# amplifier2.net
KiCad netlist of a schematic drawn in EAGLE
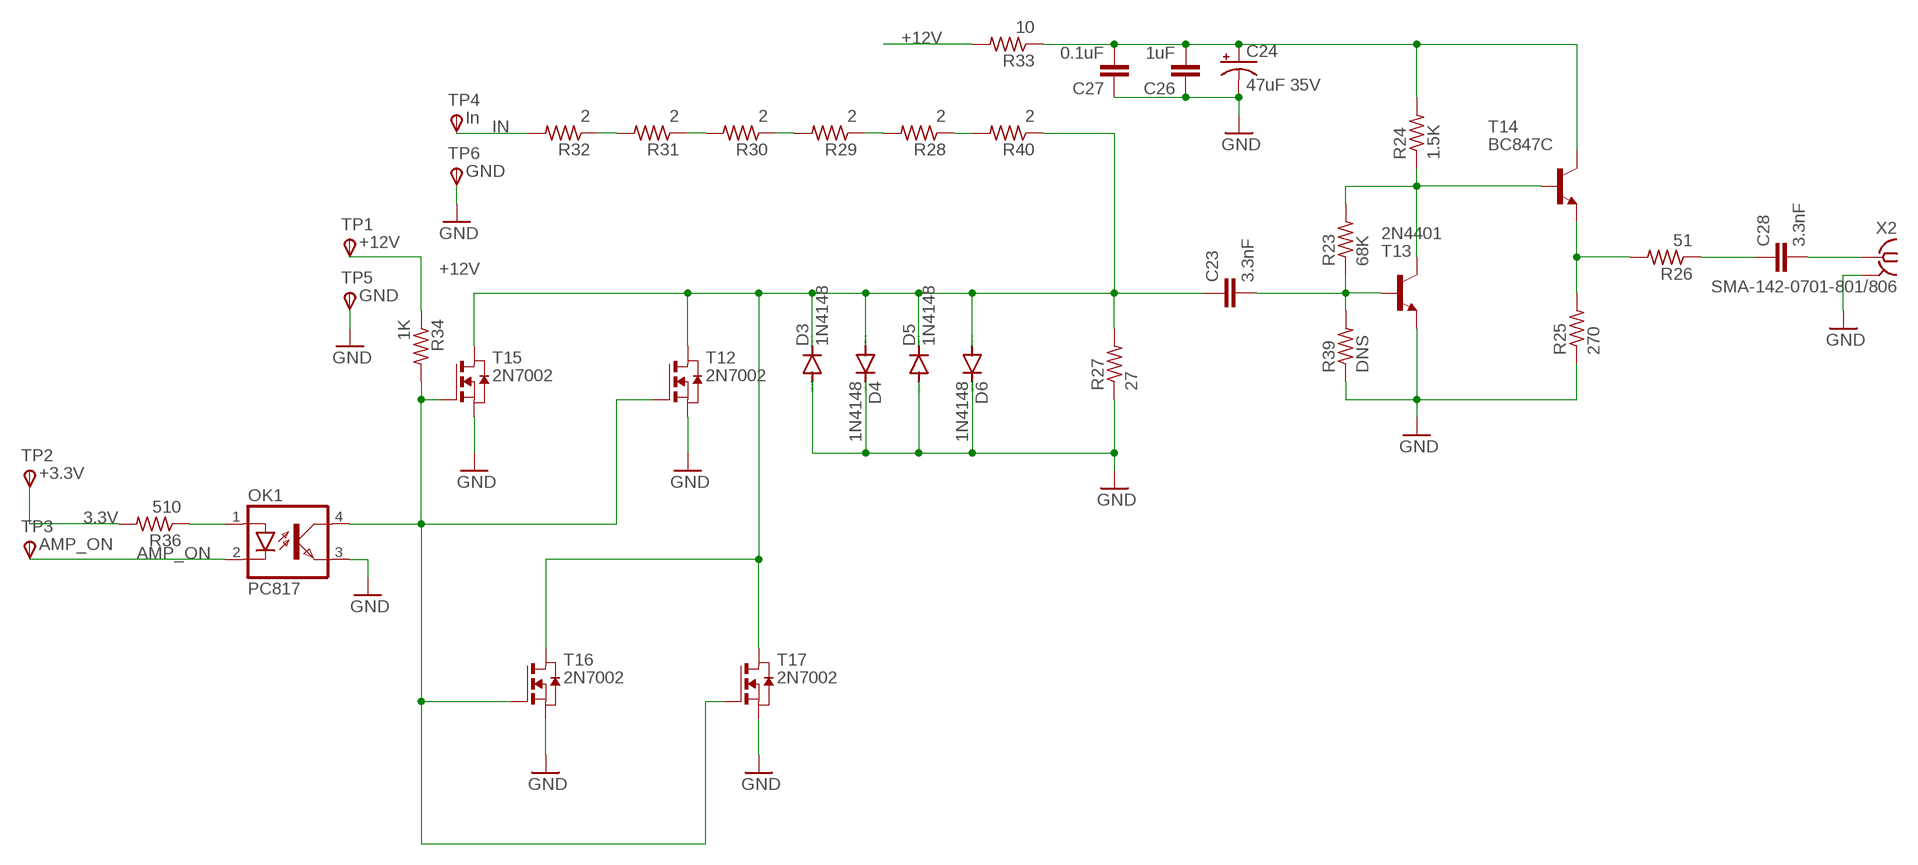
[diagram p0: schematic, sheet 1]

(export (version "E")
  (design (tool "Eeschema 10.0.6"))
  (components
    (comp (ref "C23")
      (value "3.3nF")
      (footprint "eagle-import:C0805")
      (libsource (lib "eagle-import") (part "C-EUC0805"))
    )
    (comp (ref "C24")
      (value "47uF 35V")
      (footprint "eagle-import:153CLV-1010")
      (libsource (lib "eagle-import") (part "CPOL-US153CLV-1010"))
    )
    (comp (ref "C26")
      (value "1uF")
      (footprint "eagle-import:C0805")
      (libsource (lib "eagle-import") (part "C-EUC0805"))
    )
    (comp (ref "C27")
      (value "0.1uF")
      (footprint "eagle-import:C0805")
      (libsource (lib "eagle-import") (part "C-EUC0805"))
    )
    (comp (ref "C28")
      (value "3.3nF")
      (footprint "eagle-import:C0805")
      (libsource (lib "eagle-import") (part "C-EUC0805"))
    )
    (comp (ref "D3")
      (value "1N4148")
      (footprint "eagle-import:MINIMELF")
      (libsource (lib "eagle-import") (part "DIODE-MINIMELF"))
    )
    (comp (ref "D4")
      (value "1N4148")
      (footprint "eagle-import:MINIMELF")
      (libsource (lib "eagle-import") (part "DIODE-MINIMELF"))
    )
    (comp (ref "D5")
      (value "1N4148")
      (footprint "eagle-import:MINIMELF")
      (libsource (lib "eagle-import") (part "DIODE-MINIMELF"))
    )
    (comp (ref "D6")
      (value "1N4148")
      (footprint "eagle-import:MINIMELF")
      (libsource (lib "eagle-import") (part "DIODE-MINIMELF"))
    )
    (comp (ref "OK1")
      (value "PC817")
      (footprint "eagle-import:DIL04")
      (fields (field (name "MPN") "PC817X4J000F"))
      (libsource (lib "eagle-import") (part "PC817"))
    )
    (comp (ref "R23")
      (value "68K")
      (footprint "eagle-import:R1206W")
      (libsource (lib "eagle-import") (part "R-US_R1206W"))
    )
    (comp (ref "R24")
      (value "1.5K")
      (footprint "eagle-import:R1206W")
      (libsource (lib "eagle-import") (part "R-US_R1206W"))
    )
    (comp (ref "R25")
      (value "270")
      (footprint "eagle-import:R1206W")
      (libsource (lib "eagle-import") (part "R-US_R1206W"))
    )
    (comp (ref "R26")
      (value "51")
      (footprint "eagle-import:R1206W")
      (libsource (lib "eagle-import") (part "R-US_R1206W"))
    )
    (comp (ref "R27")
      (value "27")
      (footprint "eagle-import:R1206W")
      (libsource (lib "eagle-import") (part "R-US_R1206W"))
    )
    (comp (ref "R28")
      (value "2")
      (footprint "eagle-import:R1206W")
      (libsource (lib "eagle-import") (part "R-US_R1206W"))
    )
    (comp (ref "R29")
      (value "2")
      (footprint "eagle-import:R1206W")
      (libsource (lib "eagle-import") (part "R-US_R1206W"))
    )
    (comp (ref "R30")
      (value "2")
      (footprint "eagle-import:R1206W")
      (libsource (lib "eagle-import") (part "R-US_R1206W"))
    )
    (comp (ref "R31")
      (value "2")
      (footprint "eagle-import:R1206W")
      (libsource (lib "eagle-import") (part "R-US_R1206W"))
    )
    (comp (ref "R32")
      (value "2")
      (footprint "eagle-import:R1206W")
      (libsource (lib "eagle-import") (part "R-US_R1206W"))
    )
    (comp (ref "R33")
      (value "10")
      (footprint "eagle-import:R1206W")
      (libsource (lib "eagle-import") (part "R-US_R1206W"))
    )
    (comp (ref "R34")
      (value "1K")
      (footprint "eagle-import:R1206W")
      (libsource (lib "eagle-import") (part "R-US_R1206W"))
    )
    (comp (ref "R36")
      (value "510")
      (footprint "eagle-import:R1206W")
      (libsource (lib "eagle-import") (part "R-US_R1206W"))
    )
    (comp (ref "R39")
      (value "DNS")
      (footprint "eagle-import:R1206W")
      (libsource (lib "eagle-import") (part "R-US_R1206W"))
    )
    (comp (ref "R40")
      (value "2")
      (footprint "eagle-import:R1206W")
      (libsource (lib "eagle-import") (part "R-US_R1206W"))
    )
    (comp (ref "T12")
      (value "2N7002")
      (footprint "eagle-import:SOT-23")
      (libsource (lib "eagle-import") (part "NMOSSOT23"))
    )
    (comp (ref "T13")
      (value "2N4401")
      (footprint "eagle-import:TO92-EBC")
      (libsource (lib "eagle-import") (part "-NPN-TO92-EBC2N4401"))
    )
    (comp (ref "T14")
      (value "BC847C")
      (footprint "eagle-import:SOT23-BEC")
      (libsource (lib "eagle-import") (part "transistor_402_-NPN-SOT23-BECBC847C"))
    )
    (comp (ref "T15")
      (value "2N7002")
      (footprint "eagle-import:SOT-23")
      (libsource (lib "eagle-import") (part "NMOSSOT23"))
    )
    (comp (ref "T16")
      (value "2N7002")
      (footprint "eagle-import:SOT-23")
      (libsource (lib "eagle-import") (part "NMOSSOT23"))
    )
    (comp (ref "T17")
      (value "2N7002")
      (footprint "eagle-import:SOT-23")
      (libsource (lib "eagle-import") (part "NMOSSOT23"))
    )
    (comp (ref "TP1")
      (value "TPSB2,54")
      (footprint "eagle-import:B2,54")
      (fields (field (name "TP_SIGNAL_NAME") "+12V"))
      (libsource (lib "eagle-import") (part "TPSB2,54"))
    )
    (comp (ref "TP2")
      (value "TPSB2,54")
      (footprint "eagle-import:B2,54")
      (fields (field (name "TP_SIGNAL_NAME") "+3.3V"))
      (libsource (lib "eagle-import") (part "TPSB2,54"))
    )
    (comp (ref "TP3")
      (value "TPSB2,54")
      (footprint "eagle-import:B2,54")
      (fields (field (name "TP_SIGNAL_NAME") "AMP_ON"))
      (libsource (lib "eagle-import") (part "TPSB2,54"))
    )
    (comp (ref "TP4")
      (value "TPSB2,54")
      (footprint "eagle-import:B2,54")
      (fields (field (name "TP_SIGNAL_NAME") "In"))
      (libsource (lib "eagle-import") (part "TPSB2,54"))
    )
    (comp (ref "TP5")
      (value "TPSB2,54")
      (footprint "eagle-import:B2,54")
      (fields (field (name "TP_SIGNAL_NAME") "GND"))
      (libsource (lib "eagle-import") (part "TPSB2,54"))
    )
    (comp (ref "TP6")
      (value "TPSB2,54")
      (footprint "eagle-import:B2,54")
      (fields (field (name "TP_SIGNAL_NAME") "GND"))
      (libsource (lib "eagle-import") (part "TPSB2,54"))
    )
    (comp (ref "X2")
      (value "SMA-142-0701-801/806")
      (footprint "eagle-import:J502-ND-142-0701-801_806")
      (fields (field (name "MF") "JOHNSON COMPONENTS") (field (name "MPN") "142-0701-801"))
      (libsource (lib "eagle-import") (part "SMA-142-0701-801/806"))
    )
  )
  (nets
    (net (code "1") (name "/+12V") (class "Default")
      (node (ref "R33") (pin "2") (pinfunction "2_2") (pintype "passive"))
      (node (ref "R34") (pin "1") (pinfunction "1_1") (pintype "passive"))
      (node (ref "TP1") (pin "TP") (pinfunction "PP_TP") (pintype "input"))
    )
    (net (code "2") (name "/3.3V") (class "Default")
      (node (ref "R36") (pin "2") (pinfunction "2_2") (pintype "passive"))
      (node (ref "TP2") (pin "TP") (pinfunction "PP_TP") (pintype "input"))
    )
    (net (code "3") (name "/AMP_ON") (class "Default")
      (node (ref "OK1") (pin "2") (pinfunction "C_2") (pintype "passive"))
      (node (ref "TP3") (pin "TP") (pinfunction "PP_TP") (pintype "input"))
    )
    (net (code "4") (name "/IN") (class "Default")
      (node (ref "R32") (pin "2") (pinfunction "2_2") (pintype "passive"))
      (node (ref "TP4") (pin "TP") (pinfunction "PP_TP") (pintype "input"))
    )
    (net (code "5") (name "GND") (class "Default")
      (node (ref "C24") (pin "-") (pinfunction "-_-") (pintype "passive"))
      (node (ref "C26") (pin "1") (pinfunction "1_1") (pintype "passive"))
      (node (ref "C27") (pin "1") (pinfunction "1_1") (pintype "passive"))
      (node (ref "D3") (pin "A") (pinfunction "A_A") (pintype "passive"))
      (node (ref "D4") (pin "C") (pinfunction "C_C") (pintype "passive"))
      (node (ref "D5") (pin "A") (pinfunction "A_A") (pintype "passive"))
      (node (ref "D6") (pin "C") (pinfunction "C_C") (pintype "passive"))
      (node (ref "OK1") (pin "3") (pinfunction "EMIT_3") (pintype "passive"))
      (node (ref "R25") (pin "1") (pinfunction "1_1") (pintype "passive"))
      (node (ref "R27") (pin "1") (pinfunction "1_1") (pintype "passive"))
      (node (ref "R39") (pin "1") (pinfunction "1_1") (pintype "passive"))
      (node (ref "T12") (pin "2") (pinfunction "S_2") (pintype "passive"))
      (node (ref "T13") (pin "E") (pinfunction "E_E") (pintype "passive"))
      (node (ref "T15") (pin "2") (pinfunction "S_2") (pintype "passive"))
      (node (ref "T16") (pin "2") (pinfunction "S_2") (pintype "passive"))
      (node (ref "T17") (pin "2") (pinfunction "S_2") (pintype "passive"))
      (node (ref "TP5") (pin "TP") (pinfunction "PP_TP") (pintype "input"))
      (node (ref "TP6") (pin "TP") (pinfunction "PP_TP") (pintype "input"))
      (node (ref "X2") (pin "G@1") (pinfunction "2_G@1") (pintype "passive"))
      (node (ref "X2") (pin "G@2") (pinfunction "2_G@2") (pintype "passive"))
      (node (ref "X2") (pin "G@3") (pinfunction "2_G@3") (pintype "passive"))
      (node (ref "X2") (pin "G@4") (pinfunction "2_G@4") (pintype "passive"))
    )
    (net (code "6") (name "Net-(C23-Pad2)") (class "Default")
      (node (ref "C23") (pin "2") (pinfunction "2_2") (pintype "passive"))
      (node (ref "R23") (pin "1") (pinfunction "1_1") (pintype "passive"))
      (node (ref "R39") (pin "2") (pinfunction "2_2") (pintype "passive"))
      (node (ref "T13") (pin "B") (pinfunction "B_B") (pintype "passive"))
    )
    (net (code "7") (name "Net-(C24-Pad+)") (class "Default")
      (node (ref "C24") (pin "+") (pinfunction "+_+") (pintype "passive"))
      (node (ref "C26") (pin "2") (pinfunction "2_2") (pintype "passive"))
      (node (ref "C27") (pin "2") (pinfunction "2_2") (pintype "passive"))
      (node (ref "R24") (pin "2") (pinfunction "2_2") (pintype "passive"))
      (node (ref "R33") (pin "1") (pinfunction "1_1") (pintype "passive"))
      (node (ref "T14") (pin "C") (pinfunction "C_C") (pintype "passive"))
    )
    (net (code "8") (name "Net-(C28-Pad1)") (class "Default")
      (node (ref "C28") (pin "1") (pinfunction "1_1") (pintype "passive"))
      (node (ref "R26") (pin "1") (pinfunction "1_1") (pintype "passive"))
    )
    (net (code "9") (name "Net-(C28-Pad2)") (class "Default")
      (node (ref "C28") (pin "2") (pinfunction "2_2") (pintype "passive"))
      (node (ref "X2") (pin "1") (pinfunction "1_1") (pintype "passive"))
    )
    (net (code "10") (name "Net-(OK1-A)") (class "Default")
      (node (ref "OK1") (pin "1") (pinfunction "A_1") (pintype "passive"))
      (node (ref "R36") (pin "1") (pinfunction "1_1") (pintype "passive"))
    )
    (net (code "11") (name "Net-(OK1-COL)") (class "Default")
      (node (ref "OK1") (pin "4") (pinfunction "COL_4") (pintype "passive"))
      (node (ref "R34") (pin "2") (pinfunction "2_2") (pintype "passive"))
      (node (ref "T12") (pin "3") (pinfunction "G_3") (pintype "passive"))
      (node (ref "T15") (pin "3") (pinfunction "G_3") (pintype "passive"))
      (node (ref "T16") (pin "3") (pinfunction "G_3") (pintype "passive"))
      (node (ref "T17") (pin "3") (pinfunction "G_3") (pintype "passive"))
    )
    (net (code "12") (name "Net-(R23-Pad2)") (class "Default")
      (node (ref "R23") (pin "2") (pinfunction "2_2") (pintype "passive"))
      (node (ref "R24") (pin "1") (pinfunction "1_1") (pintype "passive"))
      (node (ref "T13") (pin "C") (pinfunction "C_C") (pintype "passive"))
      (node (ref "T14") (pin "B") (pinfunction "B_B") (pintype "passive"))
    )
    (net (code "13") (name "Net-(R25-Pad2)") (class "Default")
      (node (ref "R25") (pin "2") (pinfunction "2_2") (pintype "passive"))
      (node (ref "R26") (pin "2") (pinfunction "2_2") (pintype "passive"))
      (node (ref "T14") (pin "E") (pinfunction "E_E") (pintype "passive"))
    )
    (net (code "14") (name "Net-(R28-Pad1)") (class "Default")
      (node (ref "R28") (pin "1") (pinfunction "1_1") (pintype "passive"))
      (node (ref "R40") (pin "2") (pinfunction "2_2") (pintype "passive"))
    )
    (net (code "15") (name "Net-(R28-Pad2)") (class "Default")
      (node (ref "R28") (pin "2") (pinfunction "2_2") (pintype "passive"))
      (node (ref "R29") (pin "1") (pinfunction "1_1") (pintype "passive"))
    )
    (net (code "16") (name "Net-(R29-Pad2)") (class "Default")
      (node (ref "R29") (pin "2") (pinfunction "2_2") (pintype "passive"))
      (node (ref "R30") (pin "1") (pinfunction "1_1") (pintype "passive"))
    )
    (net (code "17") (name "Net-(R30-Pad2)") (class "Default")
      (node (ref "R30") (pin "2") (pinfunction "2_2") (pintype "passive"))
      (node (ref "R31") (pin "1") (pinfunction "1_1") (pintype "passive"))
    )
    (net (code "18") (name "Net-(R31-Pad2)") (class "Default")
      (node (ref "R31") (pin "2") (pinfunction "2_2") (pintype "passive"))
      (node (ref "R32") (pin "1") (pinfunction "1_1") (pintype "passive"))
    )
    (net (code "19") (name "Net-(T12-D)") (class "Default")
      (node (ref "C23") (pin "1") (pinfunction "1_1") (pintype "passive"))
      (node (ref "D3") (pin "C") (pinfunction "C_C") (pintype "passive"))
      (node (ref "D4") (pin "A") (pinfunction "A_A") (pintype "passive"))
      (node (ref "D5") (pin "C") (pinfunction "C_C") (pintype "passive"))
      (node (ref "D6") (pin "A") (pinfunction "A_A") (pintype "passive"))
      (node (ref "R27") (pin "2") (pinfunction "2_2") (pintype "passive"))
      (node (ref "R40") (pin "1") (pinfunction "1_1") (pintype "passive"))
      (node (ref "T12") (pin "1") (pinfunction "D_1") (pintype "passive"))
      (node (ref "T15") (pin "1") (pinfunction "D_1") (pintype "passive"))
      (node (ref "T16") (pin "1") (pinfunction "D_1") (pintype "passive"))
      (node (ref "T17") (pin "1") (pinfunction "D_1") (pintype "passive"))
    )
  )
)
